# bustr_0_1.net
KiCad netlist of a schematic drawn in EAGLE
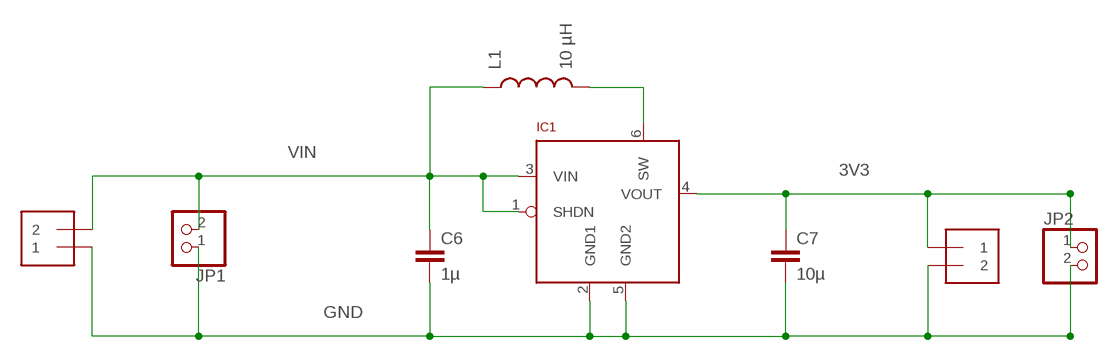
[diagram p0: schematic, sheet 1]

(export (version "E")
  (design (tool "Eeschema 10.0.6"))
  (components
    (comp (ref "C6")
      (value "1µ")
      (footprint "eagle-import:0603-CAP")
      (libsource (lib "eagle-import") (part "CAP0603-CAP"))
    )
    (comp (ref "C7")
      (value "10µ")
      (footprint "eagle-import:0805")
      (libsource (lib "eagle-import") (part "CAP0805"))
    )
    (comp (ref "IC1")
      (value "LTC3525")
      (footprint "eagle-import:SC70")
      (libsource (lib "eagle-import") (part "LTC3525"))
    )
    (comp (ref "JP1")
      (value "PINHD-1X2")
      (footprint "eagle-import:1X02")
      (libsource (lib "eagle-import") (part "PINHD-1X2"))
    )
    (comp (ref "JP2")
      (value "PINHD-1X2")
      (footprint "eagle-import:1X02")
      (libsource (lib "eagle-import") (part "PINHD-1X2"))
    )
    (comp (ref "L1")
      (value "10 µH")
      (footprint "eagle-import:1210")
      (libsource (lib "eagle-import") (part "INDUCTOR1210"))
    )
    (comp (ref "ST1")
      (value "1X2-3.5MM")
      (footprint "eagle-import:1X2-3.5MM")
      (libsource (lib "eagle-import") (part "1X2-3.5MM"))
    )
    (comp (ref "ST2")
      (value "1X2-3.5MM")
      (footprint "eagle-import:1X2-3.5MM")
      (libsource (lib "eagle-import") (part "1X2-3.5MM"))
    )
  )
  (nets
    (net (code "1") (name "/3V3") (class "Default")
      (node (ref "C7") (pin "1") (pinfunction "1_1") (pintype "passive"))
      (node (ref "IC1") (pin "4") (pinfunction "VOUT_4") (pintype "power_in"))
      (node (ref "JP2") (pin "1") (pinfunction "1_1") (pintype "passive"))
      (node (ref "ST2") (pin "1") (pinfunction "1_1") (pintype "passive"))
    )
    (net (code "2") (name "/GND") (class "Default")
      (node (ref "C6") (pin "2") (pinfunction "2_2") (pintype "passive"))
      (node (ref "C7") (pin "2") (pinfunction "2_2") (pintype "passive"))
      (node (ref "IC1") (pin "2") (pinfunction "GND1_2") (pintype "power_in"))
      (node (ref "IC1") (pin "5") (pinfunction "GND2_5") (pintype "power_in"))
      (node (ref "JP1") (pin "1") (pinfunction "1_1") (pintype "passive"))
      (node (ref "JP2") (pin "2") (pinfunction "2_2") (pintype "passive"))
      (node (ref "ST1") (pin "1") (pinfunction "1_1") (pintype "passive"))
      (node (ref "ST2") (pin "2") (pinfunction "2_2") (pintype "passive"))
    )
    (net (code "3") (name "/VIN") (class "Default")
      (node (ref "C6") (pin "1") (pinfunction "1_1") (pintype "passive"))
      (node (ref "IC1") (pin "1") (pinfunction "SHDN_1") (pintype "input"))
      (node (ref "IC1") (pin "3") (pinfunction "VIN_3") (pintype "tri_state"))
      (node (ref "JP1") (pin "2") (pinfunction "2_2") (pintype "passive"))
      (node (ref "L1") (pin "1") (pinfunction "1_1") (pintype "passive"))
      (node (ref "ST1") (pin "2") (pinfunction "2_2") (pintype "passive"))
    )
    (net (code "4") (name "Net-(IC1-SW)") (class "Default")
      (node (ref "IC1") (pin "6") (pinfunction "SW_6") (pintype "power_in"))
      (node (ref "L1") (pin "2") (pinfunction "2_2") (pintype "passive"))
    )
  )
)
